# FAL6567g.net
KiCad netlist of a schematic drawn in EAGLE
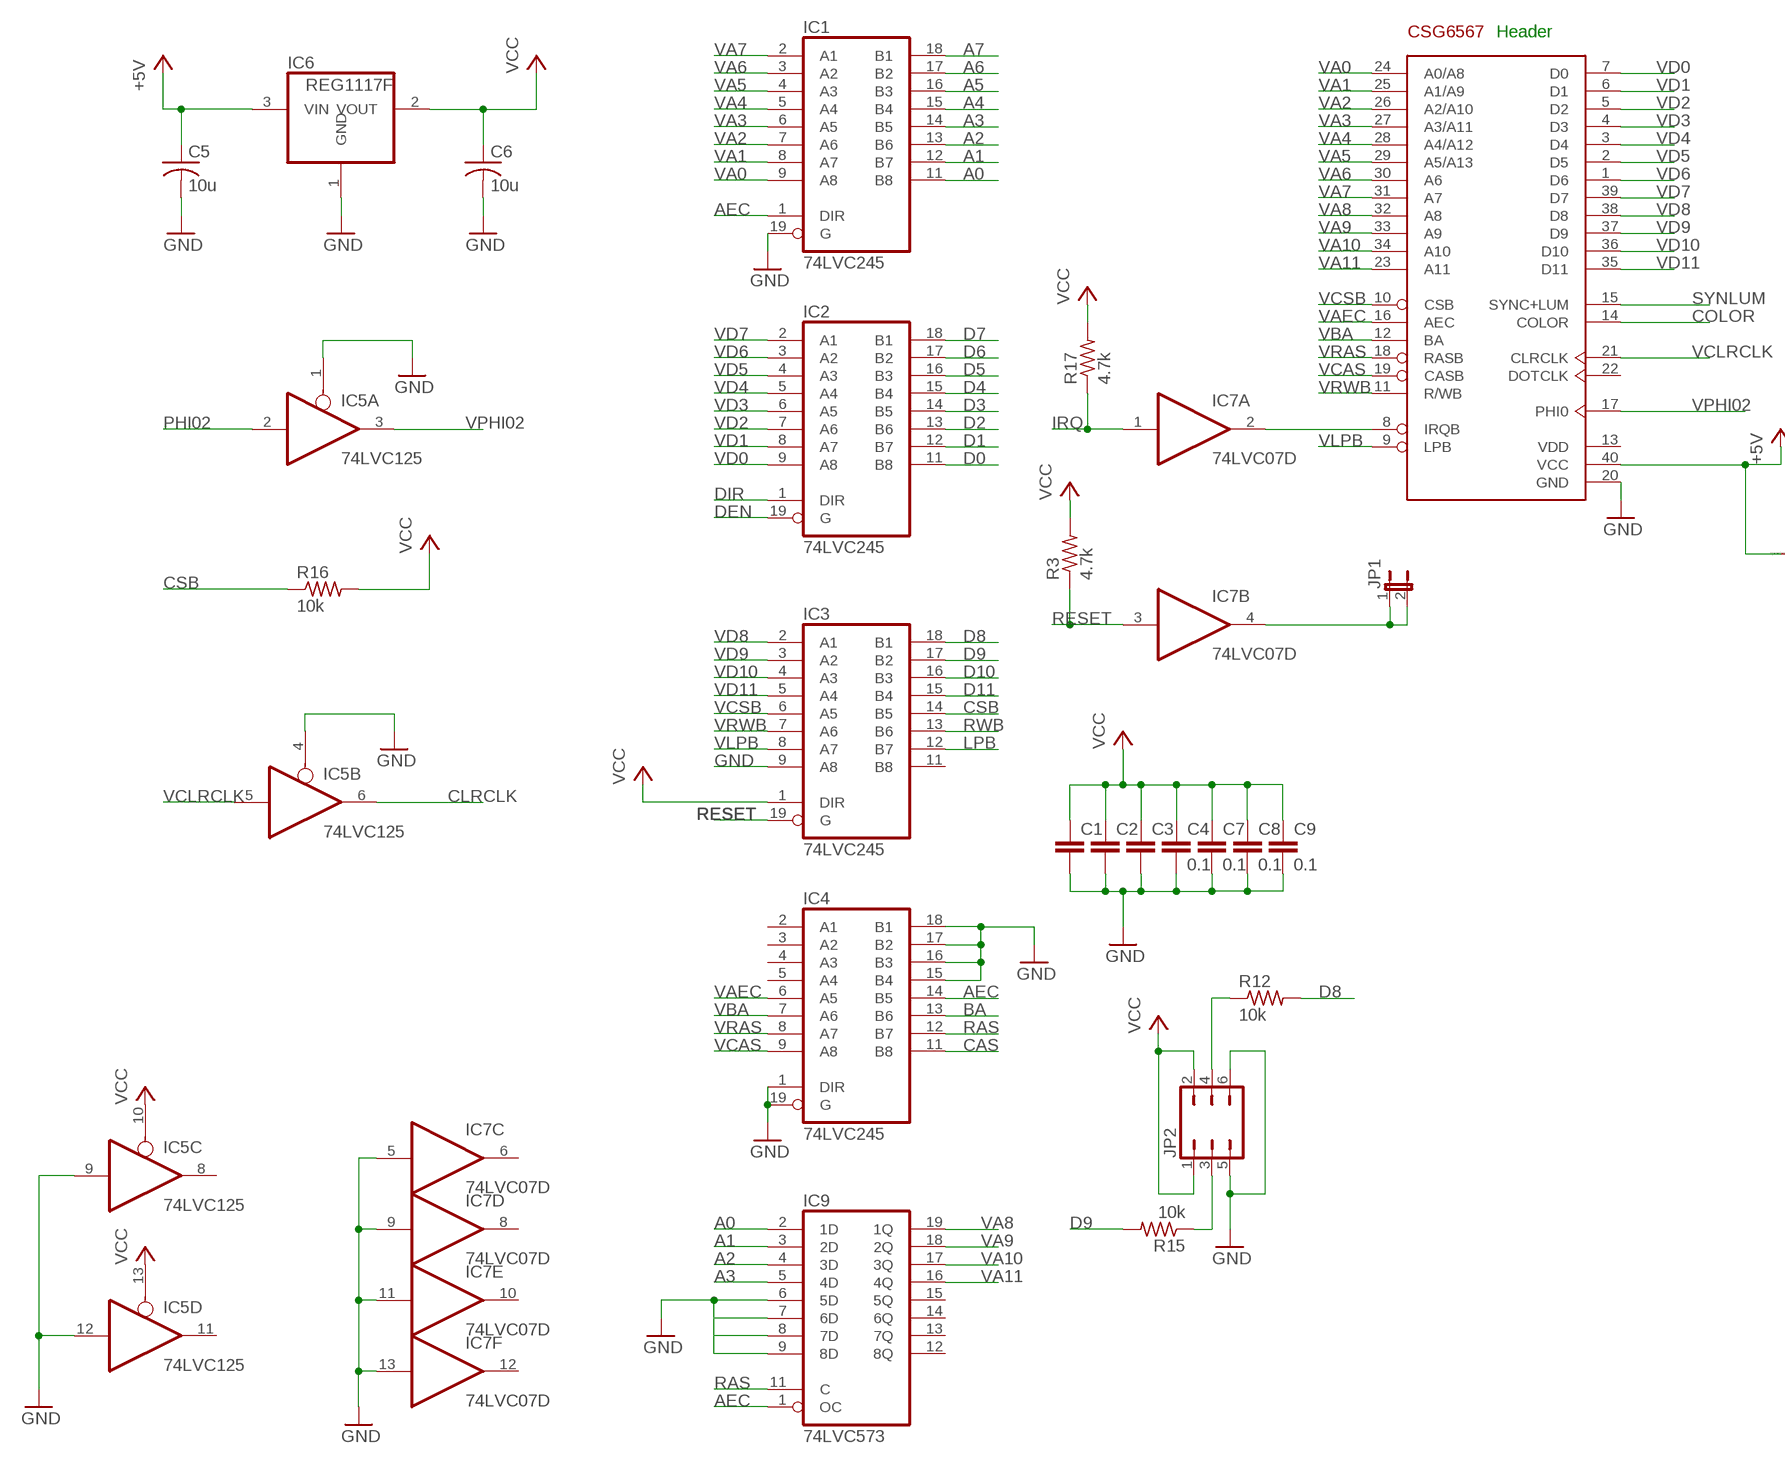
[diagram p0: schematic, sheet 1, part 1 of 2]
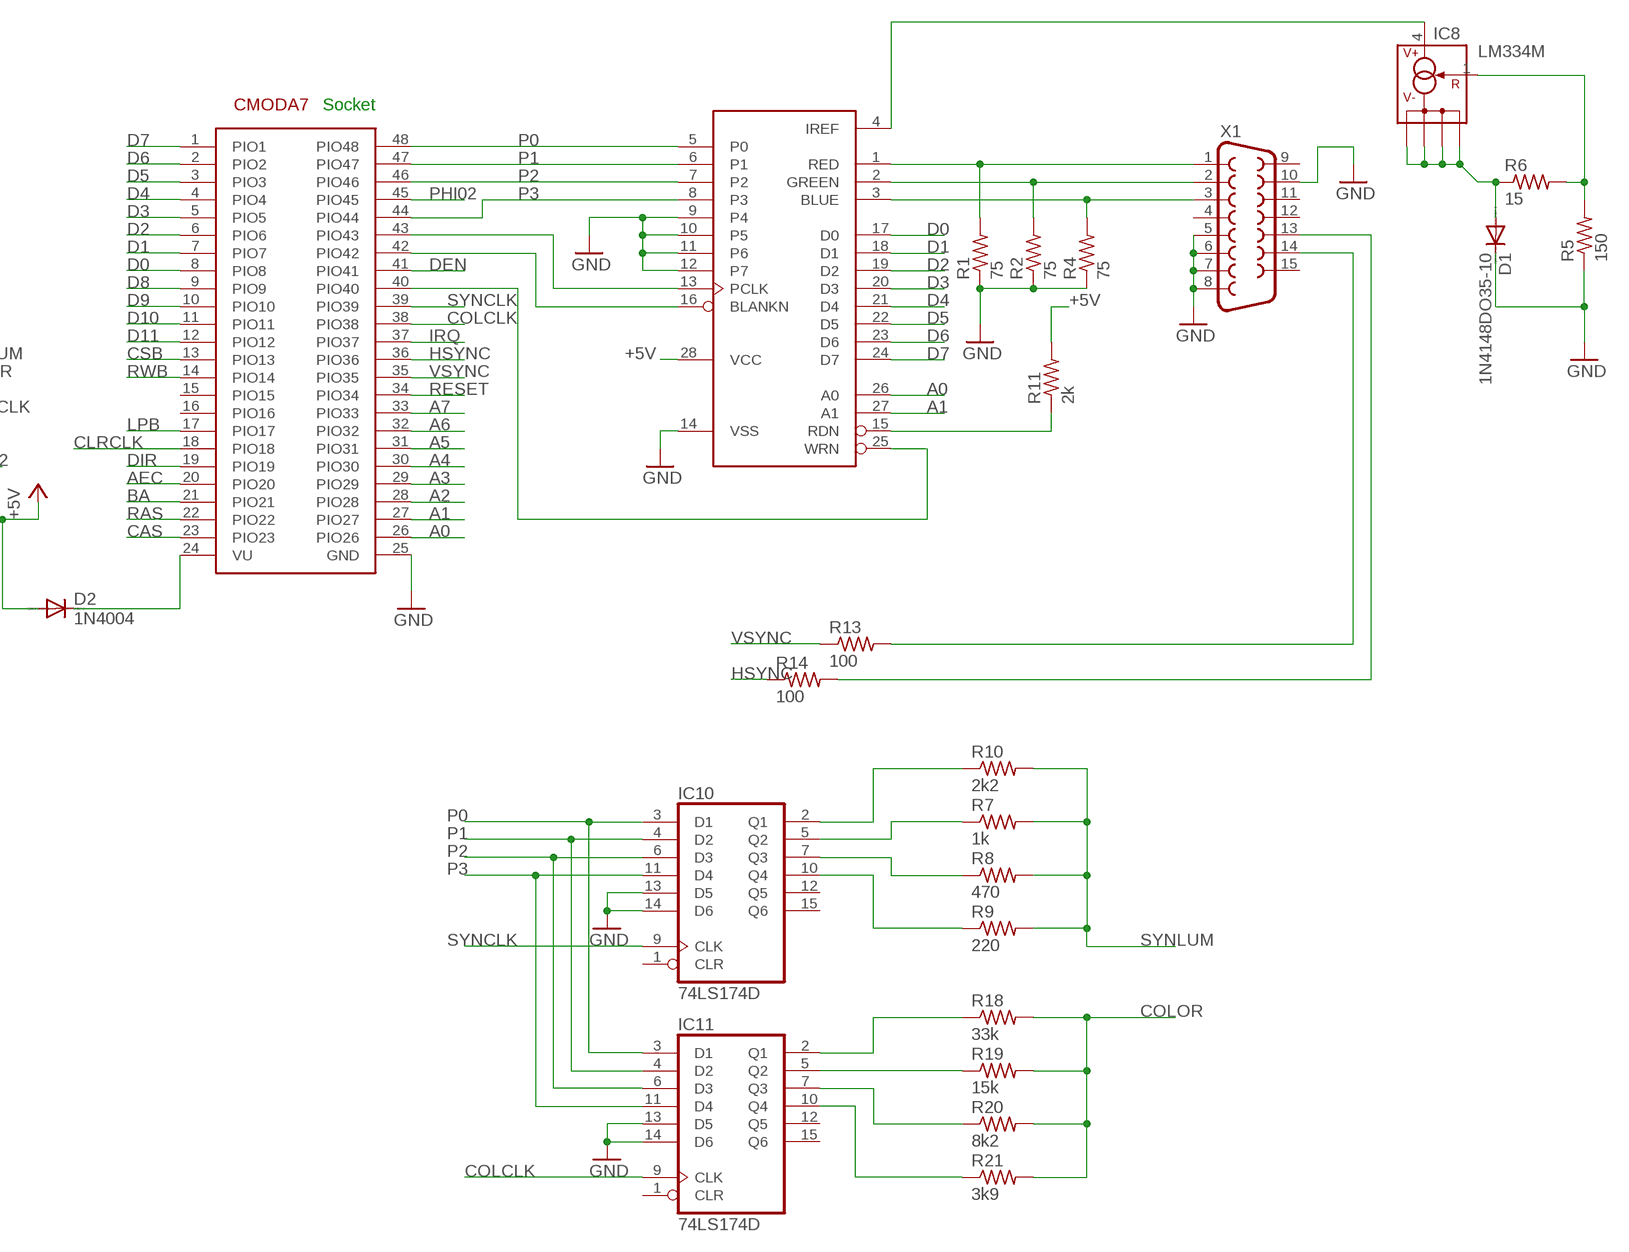
[diagram p1: schematic, sheet 1, part 2 of 2]

(export (version "E")
  (design (tool "Eeschema 10.0.6"))
  (components
    (comp (ref "C1")
      (value "C-EU050-024X044")
      (footprint "eagle-import:C050-024X044")
      (libsource (lib "eagle-import") (part "C-EU050-024X044"))
    )
    (comp (ref "C2")
      (value "C-EU050-024X044")
      (footprint "eagle-import:C050-024X044")
      (libsource (lib "eagle-import") (part "C-EU050-024X044"))
    )
    (comp (ref "C3")
      (value "C-EU050-024X044")
      (footprint "eagle-import:C050-024X044")
      (libsource (lib "eagle-import") (part "C-EU050-024X044"))
    )
    (comp (ref "C4")
      (value "0.1")
      (footprint "eagle-import:C050-024X044")
      (libsource (lib "eagle-import") (part "C-EU050-024X044"))
    )
    (comp (ref "C5")
      (value "10u")
      (footprint "eagle-import:C1206")
      (libsource (lib "eagle-import") (part "C-USC1206"))
    )
    (comp (ref "C6")
      (value "10u")
      (footprint "eagle-import:C1206")
      (libsource (lib "eagle-import") (part "C-USC1206"))
    )
    (comp (ref "C7")
      (value "0.1")
      (footprint "eagle-import:C050-024X044")
      (libsource (lib "eagle-import") (part "C-EU050-024X044"))
    )
    (comp (ref "C8")
      (value "0.1")
      (footprint "eagle-import:C050-024X044")
      (libsource (lib "eagle-import") (part "C-EU050-024X044"))
    )
    (comp (ref "C9")
      (value "0.1")
      (footprint "eagle-import:C050-024X044")
      (libsource (lib "eagle-import") (part "C-EU050-024X044"))
    )
    (comp (ref "D1")
      (value "1N4148DO35-10")
      (footprint "eagle-import:DO35-10")
      (libsource (lib "eagle-import") (part "1N4148DO35-10"))
    )
    (comp (ref "D2")
      (value "1N4004")
      (footprint "eagle-import:DO41-10")
      (libsource (lib "eagle-import") (part "1N4004"))
    )
    (comp (ref "IC1")
      (value "74LVC245")
      (footprint "eagle-import:SO20W")
      (libsource (lib "eagle-import") (part "74245DWLS"))
    )
    (comp (ref "IC2")
      (value "74LVC245")
      (footprint "eagle-import:SO20W")
      (libsource (lib "eagle-import") (part "74245DWLS"))
    )
    (comp (ref "IC3")
      (value "74LVC245")
      (footprint "eagle-import:SO20W")
      (libsource (lib "eagle-import") (part "74245DWLS"))
    )
    (comp (ref "IC4")
      (value "74LVC245")
      (footprint "eagle-import:SO20W")
      (libsource (lib "eagle-import") (part "74245DWLS"))
    )
    (comp (ref "IC5")
      (value "74LVC125")
      (footprint "eagle-import:SO14")
      (libsource (lib "eagle-import") (part "74125LVC"))
    )
    (comp (ref "IC6")
      (value "REG1117F")
      (footprint "eagle-import:DD-3")
      (fields (field (name "MF") "TEXAS INSTRUMENTS") (field (name "MPN") "REG1117FAKTTT"))
      (libsource (lib "eagle-import") (part "REG1117F"))
    )
    (comp (ref "IC7")
      (value "74LVC07D")
      (footprint "eagle-import:SO14")
      (libsource (lib "eagle-import") (part "7407DLS"))
    )
    (comp (ref "IC8")
      (value "LM334M")
      (footprint "eagle-import:SO08")
      (libsource (lib "eagle-import") (part "LM334M"))
    )
    (comp (ref "IC9")
      (value "74LVC573")
      (footprint "eagle-import:SO20W")
      (libsource (lib "eagle-import") (part "74573LVC"))
    )
    (comp (ref "IC10")
      (value "74LS174D")
      (footprint "eagle-import:SO16")
      (libsource (lib "eagle-import") (part "74174DLS"))
    )
    (comp (ref "IC11")
      (value "74LS174D")
      (footprint "eagle-import:SO16")
      (libsource (lib "eagle-import") (part "74174DLS"))
    )
    (comp (ref "JP1")
      (value "JP1E")
      (footprint "eagle-import:JP1")
      (libsource (lib "eagle-import") (part "JP1E"))
    )
    (comp (ref "JP2")
      (value "JP3Q")
      (footprint "eagle-import:JP3Q")
      (libsource (lib "eagle-import") (part "JP3Q"))
    )
    (comp (ref "R1")
      (value "75")
      (footprint "eagle-import:0204_7")
      (libsource (lib "eagle-import") (part "R-US_0204/7"))
    )
    (comp (ref "R2")
      (value "75")
      (footprint "eagle-import:0204_7")
      (libsource (lib "eagle-import") (part "R-US_0204/7"))
    )
    (comp (ref "R3")
      (value "4.7k")
      (footprint "eagle-import:0204_7")
      (libsource (lib "eagle-import") (part "R-US_0204/7"))
    )
    (comp (ref "R4")
      (value "75")
      (footprint "eagle-import:0204_7")
      (libsource (lib "eagle-import") (part "R-US_0204/7"))
    )
    (comp (ref "R5")
      (value "150")
      (footprint "eagle-import:0204_7")
      (libsource (lib "eagle-import") (part "R-US_0204/7"))
    )
    (comp (ref "R6")
      (value "15")
      (footprint "eagle-import:0204_7")
      (libsource (lib "eagle-import") (part "R-US_0204/7"))
    )
    (comp (ref "R7")
      (value "1k")
      (footprint "eagle-import:0204_7")
      (libsource (lib "eagle-import") (part "R-US_0204/7"))
    )
    (comp (ref "R8")
      (value "470")
      (footprint "eagle-import:0204_7")
      (libsource (lib "eagle-import") (part "R-US_0204/7"))
    )
    (comp (ref "R9")
      (value "220")
      (footprint "eagle-import:0204_7")
      (libsource (lib "eagle-import") (part "R-US_0204/7"))
    )
    (comp (ref "R10")
      (value "2k2")
      (footprint "eagle-import:0204_7")
      (libsource (lib "eagle-import") (part "R-US_0204/7"))
    )
    (comp (ref "R11")
      (value "2k")
      (footprint "eagle-import:0204_7")
      (libsource (lib "eagle-import") (part "R-US_0204/7"))
    )
    (comp (ref "R12")
      (value "10k")
      (footprint "eagle-import:0204_7")
      (libsource (lib "eagle-import") (part "R-US_0204/7"))
    )
    (comp (ref "R13")
      (value "100")
      (footprint "eagle-import:0204_7")
      (libsource (lib "eagle-import") (part "R-US_0204/7"))
    )
    (comp (ref "R14")
      (value "100")
      (footprint "eagle-import:0204_7")
      (libsource (lib "eagle-import") (part "R-US_0204/7"))
    )
    (comp (ref "R15")
      (value "10k")
      (footprint "eagle-import:0204_7")
      (libsource (lib "eagle-import") (part "R-US_0204/7"))
    )
    (comp (ref "R16")
      (value "10k")
      (footprint "eagle-import:0204_7")
      (libsource (lib "eagle-import") (part "R-US_0204/7"))
    )
    (comp (ref "R17")
      (value "4.7k")
      (footprint "eagle-import:0204_7")
      (libsource (lib "eagle-import") (part "R-US_0204/7"))
    )
    (comp (ref "R18")
      (value "33k")
      (footprint "eagle-import:0204_7")
      (libsource (lib "eagle-import") (part "R-US_0204/7"))
    )
    (comp (ref "R19")
      (value "15k")
      (footprint "eagle-import:0204_7")
      (libsource (lib "eagle-import") (part "R-US_0204/7"))
    )
    (comp (ref "R20")
      (value "8k2")
      (footprint "eagle-import:0204_7")
      (libsource (lib "eagle-import") (part "R-US_0204/7"))
    )
    (comp (ref "R21")
      (value "3k9")
      (footprint "eagle-import:0204_7")
      (libsource (lib "eagle-import") (part "R-US_0204/7"))
    )
    (comp (ref "U$1")
      (value "CSG6567")
      (footprint "eagle-import:DIP-40")
      (libsource (lib "eagle-import") (part "CSG6567"))
    )
    (comp (ref "U$2")
      (value "CMODA7")
      (footprint "eagle-import:DIL48")
      (libsource (lib "eagle-import") (part "CMODA7"))
    )
    (comp (ref "U$3")
      (value "ADV476")
      (footprint "eagle-import:DIL28-6")
      (libsource (lib "eagle-import") (part "ADV476"))
    )
    (comp (ref "X1")
      (value "F15HDV")
      (footprint "eagle-import:HDF15V")
      (libsource (lib "eagle-import") (part "F15HDV"))
    )
  )
  (nets
    (net (code "1") (name "+5V") (class "Default")
      (node (ref "C5") (pin "1") (pinfunction "1_1") (pintype "passive"))
      (node (ref "D2") (pin "A") (pinfunction "A_A") (pintype "passive"))
      (node (ref "IC6") (pin "3") (pinfunction "VIN_3") (pintype "input"))
      (node (ref "R11") (pin "2") (pinfunction "2_2") (pintype "passive"))
      (node (ref "U$1") (pin "40") (pinfunction "VCC_40") (pintype "power_in"))
      (node (ref "U$3") (pin "28") (pinfunction "VCC_28") (pintype "power_in"))
    )
    (net (code "2") (name "/A0") (class "Default")
      (node (ref "IC1") (pin "11") (pinfunction "B8_11") (pintype "bidirectional"))
      (node (ref "IC9") (pin "2") (pinfunction "1D_2") (pintype "input"))
      (node (ref "U$2") (pin "26") (pinfunction "PIO26_26") (pintype "bidirectional"))
      (node (ref "U$3") (pin "26") (pinfunction "A0_26") (pintype "input"))
    )
    (net (code "3") (name "/A1") (class "Default")
      (node (ref "IC1") (pin "12") (pinfunction "B7_12") (pintype "bidirectional"))
      (node (ref "IC9") (pin "3") (pinfunction "2D_3") (pintype "input"))
      (node (ref "U$2") (pin "27") (pinfunction "PIO27_27") (pintype "bidirectional"))
      (node (ref "U$3") (pin "27") (pinfunction "A1_27") (pintype "input"))
    )
    (net (code "4") (name "/A2") (class "Default")
      (node (ref "IC1") (pin "13") (pinfunction "B6_13") (pintype "bidirectional"))
      (node (ref "IC9") (pin "4") (pinfunction "3D_4") (pintype "input"))
      (node (ref "U$2") (pin "28") (pinfunction "PIO28_28") (pintype "bidirectional"))
    )
    (net (code "5") (name "/A3") (class "Default")
      (node (ref "IC1") (pin "14") (pinfunction "B5_14") (pintype "bidirectional"))
      (node (ref "IC9") (pin "5") (pinfunction "4D_5") (pintype "input"))
      (node (ref "U$2") (pin "29") (pinfunction "PIO29_29") (pintype "bidirectional"))
    )
    (net (code "6") (name "/A4") (class "Default")
      (node (ref "IC1") (pin "15") (pinfunction "B4_15") (pintype "bidirectional"))
      (node (ref "U$2") (pin "30") (pinfunction "PIO30_30") (pintype "bidirectional"))
    )
    (net (code "7") (name "/A5") (class "Default")
      (node (ref "IC1") (pin "16") (pinfunction "B3_16") (pintype "bidirectional"))
      (node (ref "U$2") (pin "31") (pinfunction "PIO31_31") (pintype "bidirectional"))
    )
    (net (code "8") (name "/A6") (class "Default")
      (node (ref "IC1") (pin "17") (pinfunction "B2_17") (pintype "bidirectional"))
      (node (ref "U$2") (pin "32") (pinfunction "PIO32_32") (pintype "bidirectional"))
    )
    (net (code "9") (name "/A7") (class "Default")
      (node (ref "IC1") (pin "18") (pinfunction "B1_18") (pintype "bidirectional"))
      (node (ref "U$2") (pin "33") (pinfunction "PIO33_33") (pintype "bidirectional"))
    )
    (net (code "10") (name "/AEC") (class "Default")
      (node (ref "IC1") (pin "1") (pinfunction "DIR_1") (pintype "input"))
      (node (ref "IC4") (pin "14") (pinfunction "B5_14") (pintype "bidirectional"))
      (node (ref "IC9") (pin "1") (pinfunction "OC_1") (pintype "input"))
      (node (ref "U$2") (pin "20") (pinfunction "PIO20_20") (pintype "bidirectional"))
    )
    (net (code "11") (name "/BA") (class "Default")
      (node (ref "IC4") (pin "13") (pinfunction "B6_13") (pintype "bidirectional"))
      (node (ref "U$2") (pin "21") (pinfunction "PIO21_21") (pintype "bidirectional"))
    )
    (net (code "12") (name "/CAS") (class "Default")
      (node (ref "IC4") (pin "11") (pinfunction "B8_11") (pintype "bidirectional"))
      (node (ref "U$2") (pin "23") (pinfunction "PIO23_23") (pintype "bidirectional"))
    )
    (net (code "13") (name "/CLRCLK") (class "Default")
      (node (ref "IC5") (pin "6") (pinfunction "O_6") (pintype "tri_state"))
      (node (ref "U$2") (pin "18") (pinfunction "PIO18_18") (pintype "bidirectional"))
    )
    (net (code "14") (name "/COLCLK") (class "Default")
      (node (ref "IC11") (pin "9") (pinfunction "CLK_9") (pintype "input"))
      (node (ref "U$2") (pin "38") (pinfunction "PIO38_38") (pintype "bidirectional"))
    )
    (net (code "15") (name "/COLOR") (class "Default")
      (node (ref "R18") (pin "2") (pinfunction "2_2") (pintype "passive"))
      (node (ref "R19") (pin "2") (pinfunction "2_2") (pintype "passive"))
      (node (ref "R20") (pin "2") (pinfunction "2_2") (pintype "passive"))
      (node (ref "R21") (pin "2") (pinfunction "2_2") (pintype "passive"))
      (node (ref "U$1") (pin "14") (pinfunction "COLOR_14") (pintype "output"))
    )
    (net (code "16") (name "/CSB") (class "Default")
      (node (ref "IC3") (pin "14") (pinfunction "B5_14") (pintype "bidirectional"))
      (node (ref "R16") (pin "1") (pinfunction "1_1") (pintype "passive"))
      (node (ref "U$2") (pin "13") (pinfunction "PIO13_13") (pintype "bidirectional"))
    )
    (net (code "17") (name "/D0") (class "Default")
      (node (ref "IC2") (pin "11") (pinfunction "B8_11") (pintype "bidirectional"))
      (node (ref "U$2") (pin "8") (pinfunction "PIO8_8") (pintype "bidirectional"))
      (node (ref "U$3") (pin "17") (pinfunction "D0_17") (pintype "bidirectional"))
    )
    (net (code "18") (name "/D1") (class "Default")
      (node (ref "IC2") (pin "12") (pinfunction "B7_12") (pintype "bidirectional"))
      (node (ref "U$2") (pin "7") (pinfunction "PIO7_7") (pintype "bidirectional"))
      (node (ref "U$3") (pin "18") (pinfunction "D1_18") (pintype "bidirectional"))
    )
    (net (code "19") (name "/D2") (class "Default")
      (node (ref "IC2") (pin "13") (pinfunction "B6_13") (pintype "bidirectional"))
      (node (ref "U$2") (pin "6") (pinfunction "PIO6_6") (pintype "bidirectional"))
      (node (ref "U$3") (pin "19") (pinfunction "D2_19") (pintype "bidirectional"))
    )
    (net (code "20") (name "/D3") (class "Default")
      (node (ref "IC2") (pin "14") (pinfunction "B5_14") (pintype "bidirectional"))
      (node (ref "U$2") (pin "5") (pinfunction "PIO5_5") (pintype "bidirectional"))
      (node (ref "U$3") (pin "20") (pinfunction "D3_20") (pintype "bidirectional"))
    )
    (net (code "21") (name "/D4") (class "Default")
      (node (ref "IC2") (pin "15") (pinfunction "B4_15") (pintype "bidirectional"))
      (node (ref "U$2") (pin "4") (pinfunction "PIO4_4") (pintype "bidirectional"))
      (node (ref "U$3") (pin "21") (pinfunction "D4_21") (pintype "bidirectional"))
    )
    (net (code "22") (name "/D5") (class "Default")
      (node (ref "IC2") (pin "16") (pinfunction "B3_16") (pintype "bidirectional"))
      (node (ref "U$2") (pin "3") (pinfunction "PIO3_3") (pintype "bidirectional"))
      (node (ref "U$3") (pin "22") (pinfunction "D5_22") (pintype "bidirectional"))
    )
    (net (code "23") (name "/D6") (class "Default")
      (node (ref "IC2") (pin "17") (pinfunction "B2_17") (pintype "bidirectional"))
      (node (ref "U$2") (pin "2") (pinfunction "PIO2_2") (pintype "bidirectional"))
      (node (ref "U$3") (pin "23") (pinfunction "D6_23") (pintype "bidirectional"))
    )
    (net (code "24") (name "/D7") (class "Default")
      (node (ref "IC2") (pin "18") (pinfunction "B1_18") (pintype "bidirectional"))
      (node (ref "U$2") (pin "1") (pinfunction "PIO1_1") (pintype "bidirectional"))
      (node (ref "U$3") (pin "24") (pinfunction "D7_24") (pintype "bidirectional"))
    )
    (net (code "25") (name "/D8") (class "Default")
      (node (ref "IC3") (pin "18") (pinfunction "B1_18") (pintype "bidirectional"))
      (node (ref "R12") (pin "2") (pinfunction "2_2") (pintype "passive"))
      (node (ref "U$2") (pin "9") (pinfunction "PIO9_9") (pintype "bidirectional"))
    )
    (net (code "26") (name "/D9") (class "Default")
      (node (ref "IC3") (pin "17") (pinfunction "B2_17") (pintype "bidirectional"))
      (node (ref "R15") (pin "2") (pinfunction "2_2") (pintype "passive"))
      (node (ref "U$2") (pin "10") (pinfunction "PIO10_10") (pintype "bidirectional"))
    )
    (net (code "27") (name "/D10") (class "Default")
      (node (ref "IC3") (pin "16") (pinfunction "B3_16") (pintype "bidirectional"))
      (node (ref "U$2") (pin "11") (pinfunction "PIO11_11") (pintype "bidirectional"))
    )
    (net (code "28") (name "/D11") (class "Default")
      (node (ref "IC3") (pin "15") (pinfunction "B4_15") (pintype "bidirectional"))
      (node (ref "U$2") (pin "12") (pinfunction "PIO12_12") (pintype "bidirectional"))
    )
    (net (code "29") (name "/DEN") (class "Default")
      (node (ref "IC2") (pin "19") (pinfunction "G_19") (pintype "input"))
      (node (ref "U$2") (pin "41") (pinfunction "PIO41_41") (pintype "bidirectional"))
    )
    (net (code "30") (name "/DIR") (class "Default")
      (node (ref "IC2") (pin "1") (pinfunction "DIR_1") (pintype "input"))
      (node (ref "U$2") (pin "19") (pinfunction "PIO19_19") (pintype "bidirectional"))
    )
    (net (code "31") (name "/HSYNC") (class "Default")
      (node (ref "R14") (pin "1") (pinfunction "1_1") (pintype "passive"))
      (node (ref "U$2") (pin "36") (pinfunction "PIO36_36") (pintype "bidirectional"))
    )
    (net (code "32") (name "/IRQ") (class "Default")
      (node (ref "IC7") (pin "1") (pinfunction "I_1") (pintype "input"))
      (node (ref "R17") (pin "1") (pinfunction "1_1") (pintype "passive"))
      (node (ref "U$2") (pin "37") (pinfunction "PIO37_37") (pintype "bidirectional"))
    )
    (net (code "33") (name "/LPB") (class "Default")
      (node (ref "IC3") (pin "12") (pinfunction "B7_12") (pintype "bidirectional"))
      (node (ref "U$2") (pin "17") (pinfunction "PIO17_17") (pintype "bidirectional"))
    )
    (net (code "34") (name "/P0") (class "Default")
      (node (ref "IC10") (pin "3") (pinfunction "D1_3") (pintype "input"))
      (node (ref "IC11") (pin "3") (pinfunction "D1_3") (pintype "input"))
      (node (ref "U$2") (pin "48") (pinfunction "PIO48_48") (pintype "bidirectional"))
      (node (ref "U$3") (pin "5") (pinfunction "P0_5") (pintype "input"))
    )
    (net (code "35") (name "/P1") (class "Default")
      (node (ref "IC10") (pin "4") (pinfunction "D2_4") (pintype "input"))
      (node (ref "IC11") (pin "4") (pinfunction "D2_4") (pintype "input"))
      (node (ref "U$2") (pin "47") (pinfunction "PIO47_47") (pintype "bidirectional"))
      (node (ref "U$3") (pin "6") (pinfunction "P1_6") (pintype "input"))
    )
    (net (code "36") (name "/P2") (class "Default")
      (node (ref "IC10") (pin "6") (pinfunction "D3_6") (pintype "input"))
      (node (ref "IC11") (pin "6") (pinfunction "D3_6") (pintype "input"))
      (node (ref "U$2") (pin "46") (pinfunction "PIO46_46") (pintype "bidirectional"))
      (node (ref "U$3") (pin "7") (pinfunction "P2_7") (pintype "input"))
    )
    (net (code "37") (name "/P3") (class "Default")
      (node (ref "IC10") (pin "11") (pinfunction "D4_11") (pintype "input"))
      (node (ref "IC11") (pin "11") (pinfunction "D4_11") (pintype "input"))
      (node (ref "U$2") (pin "44") (pinfunction "PIO44_44") (pintype "bidirectional"))
      (node (ref "U$3") (pin "8") (pinfunction "P3_8") (pintype "input"))
    )
    (net (code "38") (name "/PHI02") (class "Default")
      (node (ref "IC5") (pin "2") (pinfunction "I_2") (pintype "input"))
      (node (ref "U$2") (pin "45") (pinfunction "PIO45_45") (pintype "bidirectional"))
    )
    (net (code "39") (name "/RAS") (class "Default")
      (node (ref "IC4") (pin "12") (pinfunction "B7_12") (pintype "bidirectional"))
      (node (ref "IC9") (pin "11") (pinfunction "C_11") (pintype "input"))
      (node (ref "U$2") (pin "22") (pinfunction "PIO22_22") (pintype "bidirectional"))
    )
    (net (code "40") (name "/RESET") (class "Default")
      (node (ref "IC3") (pin "19") (pinfunction "G_19") (pintype "input"))
      (node (ref "IC7") (pin "3") (pinfunction "I_3") (pintype "input"))
      (node (ref "R3") (pin "1") (pinfunction "1_1") (pintype "passive"))
      (node (ref "U$2") (pin "34") (pinfunction "PIO34_34") (pintype "bidirectional"))
    )
    (net (code "41") (name "/RWB") (class "Default")
      (node (ref "IC3") (pin "13") (pinfunction "B6_13") (pintype "bidirectional"))
      (node (ref "U$2") (pin "14") (pinfunction "PIO14_14") (pintype "bidirectional"))
    )
    (net (code "42") (name "/SYNCLK") (class "Default")
      (node (ref "IC10") (pin "9") (pinfunction "CLK_9") (pintype "input"))
      (node (ref "U$2") (pin "39") (pinfunction "PIO39_39") (pintype "bidirectional"))
    )
    (net (code "43") (name "/SYNLUM") (class "Default")
      (node (ref "R10") (pin "2") (pinfunction "2_2") (pintype "passive"))
      (node (ref "R7") (pin "2") (pinfunction "2_2") (pintype "passive"))
      (node (ref "R8") (pin "2") (pinfunction "2_2") (pintype "passive"))
      (node (ref "R9") (pin "2") (pinfunction "2_2") (pintype "passive"))
      (node (ref "U$1") (pin "15") (pinfunction "SYNC+LUM_15") (pintype "output"))
    )
    (net (code "44") (name "/VA0") (class "Default")
      (node (ref "IC1") (pin "9") (pinfunction "A8_9") (pintype "bidirectional"))
      (node (ref "U$1") (pin "24") (pinfunction "A0/A8_24") (pintype "bidirectional"))
    )
    (net (code "45") (name "/VA1") (class "Default")
      (node (ref "IC1") (pin "8") (pinfunction "A7_8") (pintype "bidirectional"))
      (node (ref "U$1") (pin "25") (pinfunction "A1/A9_25") (pintype "bidirectional"))
    )
    (net (code "46") (name "/VA2") (class "Default")
      (node (ref "IC1") (pin "7") (pinfunction "A6_7") (pintype "bidirectional"))
      (node (ref "U$1") (pin "26") (pinfunction "A2/A10_26") (pintype "bidirectional"))
    )
    (net (code "47") (name "/VA3") (class "Default")
      (node (ref "IC1") (pin "6") (pinfunction "A5_6") (pintype "bidirectional"))
      (node (ref "U$1") (pin "27") (pinfunction "A3/A11_27") (pintype "bidirectional"))
    )
    (net (code "48") (name "/VA4") (class "Default")
      (node (ref "IC1") (pin "5") (pinfunction "A4_5") (pintype "bidirectional"))
      (node (ref "U$1") (pin "28") (pinfunction "A4/A12_28") (pintype "bidirectional"))
    )
    (net (code "49") (name "/VA5") (class "Default")
      (node (ref "IC1") (pin "4") (pinfunction "A3_4") (pintype "bidirectional"))
      (node (ref "U$1") (pin "29") (pinfunction "A5/A13_29") (pintype "bidirectional"))
    )
    (net (code "50") (name "/VA6") (class "Default")
      (node (ref "IC1") (pin "3") (pinfunction "A2_3") (pintype "bidirectional"))
      (node (ref "U$1") (pin "30") (pinfunction "A6_30") (pintype "bidirectional"))
    )
    (net (code "51") (name "/VA7") (class "Default")
      (node (ref "IC1") (pin "2") (pinfunction "A1_2") (pintype "bidirectional"))
      (node (ref "U$1") (pin "31") (pinfunction "A7_31") (pintype "bidirectional"))
    )
    (net (code "52") (name "/VA8") (class "Default")
      (node (ref "IC9") (pin "19") (pinfunction "1Q_19") (pintype "tri_state"))
      (node (ref "U$1") (pin "32") (pinfunction "A8_32") (pintype "output"))
    )
    (net (code "53") (name "/VA9") (class "Default")
      (node (ref "IC9") (pin "18") (pinfunction "2Q_18") (pintype "tri_state"))
      (node (ref "U$1") (pin "33") (pinfunction "A9_33") (pintype "output"))
    )
    (net (code "54") (name "/VA10") (class "Default")
      (node (ref "IC9") (pin "17") (pinfunction "3Q_17") (pintype "tri_state"))
      (node (ref "U$1") (pin "34") (pinfunction "A10_34") (pintype "output"))
    )
    (net (code "55") (name "/VA11") (class "Default")
      (node (ref "IC9") (pin "16") (pinfunction "4Q_16") (pintype "tri_state"))
      (node (ref "U$1") (pin "23") (pinfunction "A11_23") (pintype "output"))
    )
    (net (code "56") (name "/VAEC") (class "Default")
      (node (ref "IC4") (pin "6") (pinfunction "A5_6") (pintype "bidirectional"))
      (node (ref "U$1") (pin "16") (pinfunction "AEC_16") (pintype "output"))
    )
    (net (code "57") (name "/VBA") (class "Default")
      (node (ref "IC4") (pin "7") (pinfunction "A6_7") (pintype "bidirectional"))
      (node (ref "U$1") (pin "12") (pinfunction "BA_12") (pintype "output"))
    )
    (net (code "58") (name "/VCAS") (class "Default")
      (node (ref "IC4") (pin "9") (pinfunction "A8_9") (pintype "bidirectional"))
      (node (ref "U$1") (pin "19") (pinfunction "CASB_19") (pintype "output"))
    )
    (net (code "59") (name "/VCLRCLK") (class "Default")
      (node (ref "IC5") (pin "5") (pinfunction "I_5") (pintype "input"))
      (node (ref "U$1") (pin "21") (pinfunction "CLRCLK_21") (pintype "input"))
    )
    (net (code "60") (name "/VCSB") (class "Default")
      (node (ref "IC3") (pin "6") (pinfunction "A5_6") (pintype "bidirectional"))
      (node (ref "U$1") (pin "10") (pinfunction "CSB_10") (pintype "input"))
    )
    (net (code "61") (name "/VD0") (class "Default")
      (node (ref "IC2") (pin "9") (pinfunction "A8_9") (pintype "bidirectional"))
      (node (ref "U$1") (pin "7") (pinfunction "D0_7") (pintype "bidirectional"))
    )
    (net (code "62") (name "/VD1") (class "Default")
      (node (ref "IC2") (pin "8") (pinfunction "A7_8") (pintype "bidirectional"))
      (node (ref "U$1") (pin "6") (pinfunction "D1_6") (pintype "bidirectional"))
    )
    (net (code "63") (name "/VD2") (class "Default")
      (node (ref "IC2") (pin "7") (pinfunction "A6_7") (pintype "bidirectional"))
      (node (ref "U$1") (pin "5") (pinfunction "D2_5") (pintype "bidirectional"))
    )
    (net (code "64") (name "/VD3") (class "Default")
      (node (ref "IC2") (pin "6") (pinfunction "A5_6") (pintype "bidirectional"))
      (node (ref "U$1") (pin "4") (pinfunction "D3_4") (pintype "bidirectional"))
    )
    (net (code "65") (name "/VD4") (class "Default")
      (node (ref "IC2") (pin "5") (pinfunction "A4_5") (pintype "bidirectional"))
      (node (ref "U$1") (pin "3") (pinfunction "D4_3") (pintype "bidirectional"))
    )
    (net (code "66") (name "/VD5") (class "Default")
      (node (ref "IC2") (pin "4") (pinfunction "A3_4") (pintype "bidirectional"))
      (node (ref "U$1") (pin "2") (pinfunction "D5_2") (pintype "bidirectional"))
    )
    (net (code "67") (name "/VD6") (class "Default")
      (node (ref "IC2") (pin "3") (pinfunction "A2_3") (pintype "bidirectional"))
      (node (ref "U$1") (pin "1") (pinfunction "D6_1") (pintype "bidirectional"))
    )
    (net (code "68") (name "/VD7") (class "Default")
      (node (ref "IC2") (pin "2") (pinfunction "A1_2") (pintype "bidirectional"))
      (node (ref "U$1") (pin "39") (pinfunction "D7_39") (pintype "bidirectional"))
    )
    (net (code "69") (name "/VD8") (class "Default")
      (node (ref "IC3") (pin "2") (pinfunction "A1_2") (pintype "bidirectional"))
      (node (ref "U$1") (pin "38") (pinfunction "D8_38") (pintype "input"))
    )
    (net (code "70") (name "/VD9") (class "Default")
      (node (ref "IC3") (pin "3") (pinfunction "A2_3") (pintype "bidirectional"))
      (node (ref "U$1") (pin "37") (pinfunction "D9_37") (pintype "input"))
    )
    (net (code "71") (name "/VD10") (class "Default")
      (node (ref "IC3") (pin "4") (pinfunction "A3_4") (pintype "bidirectional"))
      (node (ref "U$1") (pin "36") (pinfunction "D10_36") (pintype "input"))
    )
    (net (code "72") (name "/VD11") (class "Default")
      (node (ref "IC3") (pin "5") (pinfunction "A4_5") (pintype "bidirectional"))
      (node (ref "U$1") (pin "35") (pinfunction "D11_35") (pintype "input"))
    )
    (net (code "73") (name "/VDD") (class "Default")
      (node (ref "U$1") (pin "13") (pinfunction "VDD_13") (pintype "power_in"))
    )
    (net (code "74") (name "/VLPB") (class "Default")
      (node (ref "IC3") (pin "8") (pinfunction "A7_8") (pintype "bidirectional"))
      (node (ref "U$1") (pin "9") (pinfunction "LPB_9") (pintype "input"))
    )
    (net (code "75") (name "/VPHI02") (class "Default")
      (node (ref "IC5") (pin "3") (pinfunction "O_3") (pintype "tri_state"))
      (node (ref "U$1") (pin "17") (pinfunction "PHI0_17") (pintype "output"))
    )
    (net (code "76") (name "/VRAS") (class "Default")
      (node (ref "IC4") (pin "8") (pinfunction "A7_8") (pintype "bidirectional"))
      (node (ref "U$1") (pin "18") (pinfunction "RASB_18") (pintype "output"))
    )
    (net (code "77") (name "/VRWB") (class "Default")
      (node (ref "IC3") (pin "7") (pinfunction "A6_7") (pintype "bidirectional"))
      (node (ref "U$1") (pin "11") (pinfunction "R/WB_11") (pintype "input"))
    )
    (net (code "78") (name "/VSYNC") (class "Default")
      (node (ref "R13") (pin "1") (pinfunction "1_1") (pintype "passive"))
      (node (ref "U$2") (pin "35") (pinfunction "PIO35_35") (pintype "bidirectional"))
    )
    (net (code "79") (name "GND") (class "Default")
      (node (ref "C1") (pin "2") (pinfunction "2_2") (pintype "passive"))
      (node (ref "C2") (pin "2") (pinfunction "2_2") (pintype "passive"))
      (node (ref "C3") (pin "2") (pinfunction "2_2") (pintype "passive"))
      (node (ref "C4") (pin "2") (pinfunction "2_2") (pintype "passive"))
      (node (ref "C5") (pin "2") (pinfunction "2_2") (pintype "passive"))
      (node (ref "C6") (pin "2") (pinfunction "2_2") (pintype "passive"))
      (node (ref "C7") (pin "2") (pinfunction "2_2") (pintype "passive"))
      (node (ref "C8") (pin "2") (pinfunction "2_2") (pintype "passive"))
      (node (ref "C9") (pin "2") (pinfunction "2_2") (pintype "passive"))
      (node (ref "D1") (pin "C") (pinfunction "C_C") (pintype "passive"))
      (node (ref "IC1") (pin "19") (pinfunction "G_19") (pintype "input"))
      (node (ref "IC10") (pin "13") (pinfunction "D5_13") (pintype "input"))
      (node (ref "IC10") (pin "14") (pinfunction "D6_14") (pintype "input"))
      (node (ref "IC11") (pin "13") (pinfunction "D5_13") (pintype "input"))
      (node (ref "IC11") (pin "14") (pinfunction "D6_14") (pintype "input"))
      (node (ref "IC3") (pin "9") (pinfunction "A8_9") (pintype "bidirectional"))
      (node (ref "IC4") (pin "1") (pinfunction "DIR_1") (pintype "input"))
      (node (ref "IC4") (pin "15") (pinfunction "B4_15") (pintype "bidirectional"))
      (node (ref "IC4") (pin "16") (pinfunction "B3_16") (pintype "bidirectional"))
      (node (ref "IC4") (pin "17") (pinfunction "B2_17") (pintype "bidirectional"))
      (node (ref "IC4") (pin "18") (pinfunction "B1_18") (pintype "bidirectional"))
      (node (ref "IC4") (pin "19") (pinfunction "G_19") (pintype "input"))
      (node (ref "IC5") (pin "1") (pinfunction "OE_1") (pintype "input"))
      (node (ref "IC5") (pin "12") (pinfunction "I_12") (pintype "input"))
      (node (ref "IC5") (pin "4") (pinfunction "OE_4") (pintype "input"))
      (node (ref "IC5") (pin "9") (pinfunction "I_9") (pintype "input"))
      (node (ref "IC6") (pin "1") (pinfunction "GND_1") (pintype "power_in"))
      (node (ref "IC7") (pin "11") (pinfunction "I_11") (pintype "input"))
      (node (ref "IC7") (pin "13") (pinfunction "I_13") (pintype "input"))
      (node (ref "IC7") (pin "5") (pinfunction "I_5") (pintype "input"))
      (node (ref "IC7") (pin "9") (pinfunction "I_9") (pintype "input"))
      (node (ref "IC9") (pin "6") (pinfunction "5D_6") (pintype "input"))
      (node (ref "IC9") (pin "9") (pinfunction "8D_9") (pintype "input"))
      (node (ref "JP2") (pin "5") (pinfunction "5_5") (pintype "passive"))
      (node (ref "JP2") (pin "6") (pinfunction "6_6") (pintype "passive"))
      (node (ref "R1") (pin "1") (pinfunction "1_1") (pintype "passive"))
      (node (ref "R2") (pin "1") (pinfunction "1_1") (pintype "passive"))
      (node (ref "R4") (pin "1") (pinfunction "1_1") (pintype "passive"))
      (node (ref "R5") (pin "1") (pinfunction "1_1") (pintype "passive"))
      (node (ref "U$1") (pin "20") (pinfunction "GND_20") (pintype "power_in"))
      (node (ref "U$2") (pin "25") (pinfunction "GND_25") (pintype "power_in"))
      (node (ref "U$3") (pin "10") (pinfunction "P5_10") (pintype "input"))
      (node (ref "U$3") (pin "11") (pinfunction "P6_11") (pintype "input"))
      (node (ref "U$3") (pin "12") (pinfunction "P7_12") (pintype "input"))
      (node (ref "U$3") (pin "14") (pinfunction "VSS_14") (pintype "power_in"))
      (node (ref "U$3") (pin "9") (pinfunction "P4_9") (pintype "input"))
      (node (ref "X1") (pin "10") (pinfunction "10_10") (pintype "passive"))
      (node (ref "X1") (pin "5") (pinfunction "5_5") (pintype "passive"))
      (node (ref "X1") (pin "6") (pinfunction "6_6") (pintype "passive"))
      (node (ref "X1") (pin "7") (pinfunction "7_7") (pintype "passive"))
      (node (ref "X1") (pin "8") (pinfunction "8_8") (pintype "passive"))
    )
    (net (code "80") (name "Net-(D1-PadA)") (class "Default")
      (node (ref "D1") (pin "A") (pinfunction "A_A") (pintype "passive"))
      (node (ref "IC8") (pin "2") (pinfunction "V-_2") (pintype "passive"))
      (node (ref "IC8") (pin "3") (pinfunction "V-_3") (pintype "passive"))
      (node (ref "IC8") (pin "6") (pinfunction "V-_6") (pintype "passive"))
      (node (ref "IC8") (pin "7") (pinfunction "V-_7") (pintype "passive"))
      (node (ref "R6") (pin "1") (pinfunction "1_1") (pintype "passive"))
    )
    (net (code "81") (name "Net-(IC7A-O)") (class "Default")
      (node (ref "IC7") (pin "2") (pinfunction "O_2") (pintype "open_collector"))
      (node (ref "U$1") (pin "8") (pinfunction "IRQB_8") (pintype "open_collector"))
    )
    (net (code "82") (name "Net-(IC7B-O)") (class "Default")
      (node (ref "IC7") (pin "4") (pinfunction "O_4") (pintype "open_collector"))
      (node (ref "JP1") (pin "1") (pinfunction "1_1") (pintype "passive"))
      (node (ref "JP1") (pin "2") (pinfunction "2_2") (pintype "passive"))
    )
    (net (code "83") (name "Net-(IC8-R)") (class "Default")
      (node (ref "IC8") (pin "1") (pinfunction "R_1") (pintype "passive"))
      (node (ref "R5") (pin "2") (pinfunction "2_2") (pintype "passive"))
      (node (ref "R6") (pin "2") (pinfunction "2_2") (pintype "passive"))
    )
    (net (code "84") (name "Net-(IC8-V+)") (class "Default")
      (node (ref "IC8") (pin "4") (pinfunction "V+_4") (pintype "passive"))
      (node (ref "U$3") (pin "4") (pinfunction "IREF_4") (pintype "bidirectional"))
    )
    (net (code "85") (name "Net-(IC10A-Q1)") (class "Default")
      (node (ref "IC10") (pin "2") (pinfunction "Q1_2") (pintype "output"))
      (node (ref "R10") (pin "1") (pinfunction "1_1") (pintype "passive"))
    )
    (net (code "86") (name "Net-(IC10A-Q2)") (class "Default")
      (node (ref "IC10") (pin "5") (pinfunction "Q2_5") (pintype "output"))
      (node (ref "R7") (pin "1") (pinfunction "1_1") (pintype "passive"))
    )
    (net (code "87") (name "Net-(IC10A-Q3)") (class "Default")
      (node (ref "IC10") (pin "7") (pinfunction "Q3_7") (pintype "output"))
      (node (ref "R8") (pin "1") (pinfunction "1_1") (pintype "passive"))
    )
    (net (code "88") (name "Net-(IC10A-Q4)") (class "Default")
      (node (ref "IC10") (pin "10") (pinfunction "Q4_10") (pintype "output"))
      (node (ref "R9") (pin "1") (pinfunction "1_1") (pintype "passive"))
    )
    (net (code "89") (name "Net-(IC11A-Q1)") (class "Default")
      (node (ref "IC11") (pin "2") (pinfunction "Q1_2") (pintype "output"))
      (node (ref "R18") (pin "1") (pinfunction "1_1") (pintype "passive"))
    )
    (net (code "90") (name "Net-(IC11A-Q2)") (class "Default")
      (node (ref "IC11") (pin "5") (pinfunction "Q2_5") (pintype "output"))
      (node (ref "R19") (pin "1") (pinfunction "1_1") (pintype "passive"))
    )
    (net (code "91") (name "Net-(IC11A-Q3)") (class "Default")
      (node (ref "IC11") (pin "7") (pinfunction "Q3_7") (pintype "output"))
      (node (ref "R20") (pin "1") (pinfunction "1_1") (pintype "passive"))
    )
    (net (code "92") (name "Net-(IC11A-Q4)") (class "Default")
      (node (ref "IC11") (pin "10") (pinfunction "Q4_10") (pintype "output"))
      (node (ref "R21") (pin "1") (pinfunction "1_1") (pintype "passive"))
    )
    (net (code "93") (name "Net-(JP2-Pad3)") (class "Default")
      (node (ref "JP2") (pin "3") (pinfunction "3_3") (pintype "passive"))
      (node (ref "R15") (pin "1") (pinfunction "1_1") (pintype "passive"))
    )
    (net (code "94") (name "Net-(JP2-Pad4)") (class "Default")
      (node (ref "JP2") (pin "4") (pinfunction "4_4") (pintype "passive"))
      (node (ref "R12") (pin "1") (pinfunction "1_1") (pintype "passive"))
    )
    (net (code "95") (name "Net-(R13-Pad2)") (class "Default")
      (node (ref "R13") (pin "2") (pinfunction "2_2") (pintype "passive"))
      (node (ref "X1") (pin "14") (pinfunction "14_14") (pintype "passive"))
    )
    (net (code "96") (name "Net-(R14-Pad2)") (class "Default")
      (node (ref "R14") (pin "2") (pinfunction "2_2") (pintype "passive"))
      (node (ref "X1") (pin "13") (pinfunction "13_13") (pintype "passive"))
    )
    (net (code "97") (name "Net-(U$2-PIO40)") (class "Default")
      (node (ref "U$2") (pin "40") (pinfunction "PIO40_40") (pintype "bidirectional"))
      (node (ref "U$3") (pin "25") (pinfunction "WRN_25") (pintype "input"))
    )
    (net (code "98") (name "Net-(U$2-PIO42)") (class "Default")
      (node (ref "U$2") (pin "42") (pinfunction "PIO42_42") (pintype "bidirectional"))
      (node (ref "U$3") (pin "16") (pinfunction "BLANKN_16") (pintype "input"))
    )
    (net (code "99") (name "Net-(U$2-PIO43)") (class "Default")
      (node (ref "U$2") (pin "43") (pinfunction "PIO43_43") (pintype "bidirectional"))
      (node (ref "U$3") (pin "13") (pinfunction "PCLK_13") (pintype "input"))
    )
    (net (code "100") (name "Net-(U$2-VU)") (class "Default")
      (node (ref "D2") (pin "C") (pinfunction "C_C") (pintype "passive"))
      (node (ref "U$2") (pin "24") (pinfunction "VU_24") (pintype "power_in"))
    )
    (net (code "101") (name "Net-(U$3-BLUE)") (class "Default")
      (node (ref "R4") (pin "2") (pinfunction "2_2") (pintype "passive"))
      (node (ref "U$3") (pin "3") (pinfunction "BLUE_3") (pintype "output"))
      (node (ref "X1") (pin "3") (pinfunction "3_3") (pintype "passive"))
    )
    (net (code "102") (name "Net-(U$3-GREEN)") (class "Default")
      (node (ref "R2") (pin "2") (pinfunction "2_2") (pintype "passive"))
      (node (ref "U$3") (pin "2") (pinfunction "GREEN_2") (pintype "output"))
      (node (ref "X1") (pin "2") (pinfunction "2_2") (pintype "passive"))
    )
    (net (code "103") (name "Net-(U$3-RDN)") (class "Default")
      (node (ref "R11") (pin "1") (pinfunction "1_1") (pintype "passive"))
      (node (ref "U$3") (pin "15") (pinfunction "RDN_15") (pintype "input"))
    )
    (net (code "104") (name "Net-(U$3-RED)") (class "Default")
      (node (ref "R1") (pin "2") (pinfunction "2_2") (pintype "passive"))
      (node (ref "U$3") (pin "1") (pinfunction "RED_1") (pintype "output"))
      (node (ref "X1") (pin "1") (pinfunction "1_1") (pintype "passive"))
    )
    (net (code "105") (name "VCC") (class "Default")
      (node (ref "C1") (pin "1") (pinfunction "1_1") (pintype "passive"))
      (node (ref "C2") (pin "1") (pinfunction "1_1") (pintype "passive"))
      (node (ref "C3") (pin "1") (pinfunction "1_1") (pintype "passive"))
      (node (ref "C4") (pin "1") (pinfunction "1_1") (pintype "passive"))
      (node (ref "C6") (pin "1") (pinfunction "1_1") (pintype "passive"))
      (node (ref "C7") (pin "1") (pinfunction "1_1") (pintype "passive"))
      (node (ref "C8") (pin "1") (pinfunction "1_1") (pintype "passive"))
      (node (ref "C9") (pin "1") (pinfunction "1_1") (pintype "passive"))
      (node (ref "IC3") (pin "1") (pinfunction "DIR_1") (pintype "input"))
      (node (ref "IC5") (pin "10") (pinfunction "OE_10") (pintype "input"))
      (node (ref "IC5") (pin "13") (pinfunction "OE_13") (pintype "input"))
      (node (ref "IC6") (pin "2") (pinfunction "VOUT_2") (pintype "output"))
      (node (ref "JP2") (pin "1") (pinfunction "1_1") (pintype "passive"))
      (node (ref "JP2") (pin "2") (pinfunction "2_2") (pintype "passive"))
      (node (ref "R16") (pin "2") (pinfunction "2_2") (pintype "passive"))
      (node (ref "R17") (pin "2") (pinfunction "2_2") (pintype "passive"))
      (node (ref "R3") (pin "2") (pinfunction "2_2") (pintype "passive"))
    )
    (net (code "106") (name "unconnected-(IC3A-B8-Pad11)") (class "Default")
      (node (ref "IC3") (pin "11") (pinfunction "B8_11") (pintype "bidirectional"))
    )
    (net (code "107") (name "unconnected-(IC4A-A1-Pad2)") (class "Default")
      (node (ref "IC4") (pin "2") (pinfunction "A1_2") (pintype "bidirectional"))
    )
    (net (code "108") (name "unconnected-(IC4A-A2-Pad3)") (class "Default")
      (node (ref "IC4") (pin "3") (pinfunction "A2_3") (pintype "bidirectional"))
    )
    (net (code "109") (name "unconnected-(IC4A-A3-Pad4)") (class "Default")
      (node (ref "IC4") (pin "4") (pinfunction "A3_4") (pintype "bidirectional"))
    )
    (net (code "110") (name "unconnected-(IC4A-A4-Pad5)") (class "Default")
      (node (ref "IC4") (pin "5") (pinfunction "A4_5") (pintype "bidirectional"))
    )
    (net (code "111") (name "unconnected-(IC5C-O-Pad8)") (class "Default")
      (node (ref "IC5") (pin "8") (pinfunction "O_8") (pintype "tri_state"))
    )
    (net (code "112") (name "unconnected-(IC5D-O-Pad11)") (class "Default")
      (node (ref "IC5") (pin "11") (pinfunction "O_11") (pintype "tri_state"))
    )
    (net (code "113") (name "unconnected-(IC7C-O-Pad6)") (class "Default")
      (node (ref "IC7") (pin "6") (pinfunction "O_6") (pintype "open_collector"))
    )
    (net (code "114") (name "unconnected-(IC7D-O-Pad8)") (class "Default")
      (node (ref "IC7") (pin "8") (pinfunction "O_8") (pintype "open_collector"))
    )
    (net (code "115") (name "unconnected-(IC7E-O-Pad10)") (class "Default")
      (node (ref "IC7") (pin "10") (pinfunction "O_10") (pintype "open_collector"))
    )
    (net (code "116") (name "unconnected-(IC7F-O-Pad12)") (class "Default")
      (node (ref "IC7") (pin "12") (pinfunction "O_12") (pintype "open_collector"))
    )
    (net (code "117") (name "unconnected-(IC9A-5Q-Pad15)") (class "Default")
      (node (ref "IC9") (pin "15") (pinfunction "5Q_15") (pintype "tri_state"))
    )
    (net (code "118") (name "unconnected-(IC9A-6D-Pad7)") (class "Default")
      (node (ref "IC9") (pin "7") (pinfunction "6D_7") (pintype "input"))
    )
    (net (code "119") (name "unconnected-(IC9A-6Q-Pad14)") (class "Default")
      (node (ref "IC9") (pin "14") (pinfunction "6Q_14") (pintype "tri_state"))
    )
    (net (code "120") (name "unconnected-(IC9A-7D-Pad8)") (class "Default")
      (node (ref "IC9") (pin "8") (pinfunction "7D_8") (pintype "input"))
    )
    (net (code "121") (name "unconnected-(IC9A-7Q-Pad13)") (class "Default")
      (node (ref "IC9") (pin "13") (pinfunction "7Q_13") (pintype "tri_state"))
    )
    (net (code "122") (name "unconnected-(IC9A-8Q-Pad12)") (class "Default")
      (node (ref "IC9") (pin "12") (pinfunction "8Q_12") (pintype "tri_state"))
    )
    (net (code "123") (name "unconnected-(IC10A-CLR-Pad1)") (class "Default")
      (node (ref "IC10") (pin "1") (pinfunction "CLR_1") (pintype "input"))
    )
    (net (code "124") (name "unconnected-(IC10A-Q5-Pad12)") (class "Default")
      (node (ref "IC10") (pin "12") (pinfunction "Q5_12") (pintype "output"))
    )
    (net (code "125") (name "unconnected-(IC10A-Q6-Pad15)") (class "Default")
      (node (ref "IC10") (pin "15") (pinfunction "Q6_15") (pintype "output"))
    )
    (net (code "126") (name "unconnected-(IC11A-CLR-Pad1)") (class "Default")
      (node (ref "IC11") (pin "1") (pinfunction "CLR_1") (pintype "input"))
    )
    (net (code "127") (name "unconnected-(IC11A-Q5-Pad12)") (class "Default")
      (node (ref "IC11") (pin "12") (pinfunction "Q5_12") (pintype "output"))
    )
    (net (code "128") (name "unconnected-(IC11A-Q6-Pad15)") (class "Default")
      (node (ref "IC11") (pin "15") (pinfunction "Q6_15") (pintype "output"))
    )
    (net (code "129") (name "unconnected-(U$1-DOTCLK-Pad22)") (class "Default")
      (node (ref "U$1") (pin "22") (pinfunction "DOTCLK_22") (pintype "input"))
    )
    (net (code "130") (name "unconnected-(U$2-PIO15-Pad15)") (class "Default")
      (node (ref "U$2") (pin "15") (pinfunction "PIO15_15") (pintype "bidirectional"))
    )
    (net (code "131") (name "unconnected-(U$2-PIO16-Pad16)") (class "Default")
      (node (ref "U$2") (pin "16") (pinfunction "PIO16_16") (pintype "bidirectional"))
    )
    (net (code "132") (name "unconnected-(X1-Pad4)") (class "Default")
      (node (ref "X1") (pin "4") (pinfunction "4_4") (pintype "passive"))
    )
    (net (code "133") (name "unconnected-(X1-Pad9)") (class "Default")
      (node (ref "X1") (pin "9") (pinfunction "9_9") (pintype "passive"))
    )
    (net (code "134") (name "unconnected-(X1-Pad11)") (class "Default")
      (node (ref "X1") (pin "11") (pinfunction "11_11") (pintype "passive"))
    )
    (net (code "135") (name "unconnected-(X1-Pad12)") (class "Default")
      (node (ref "X1") (pin "12") (pinfunction "12_12") (pintype "passive"))
    )
    (net (code "136") (name "unconnected-(X1-Pad15)") (class "Default")
      (node (ref "X1") (pin "15") (pinfunction "15_15") (pintype "passive"))
    )
  )
)
